# untitled.net
KiCad netlist of a schematic drawn in EAGLE
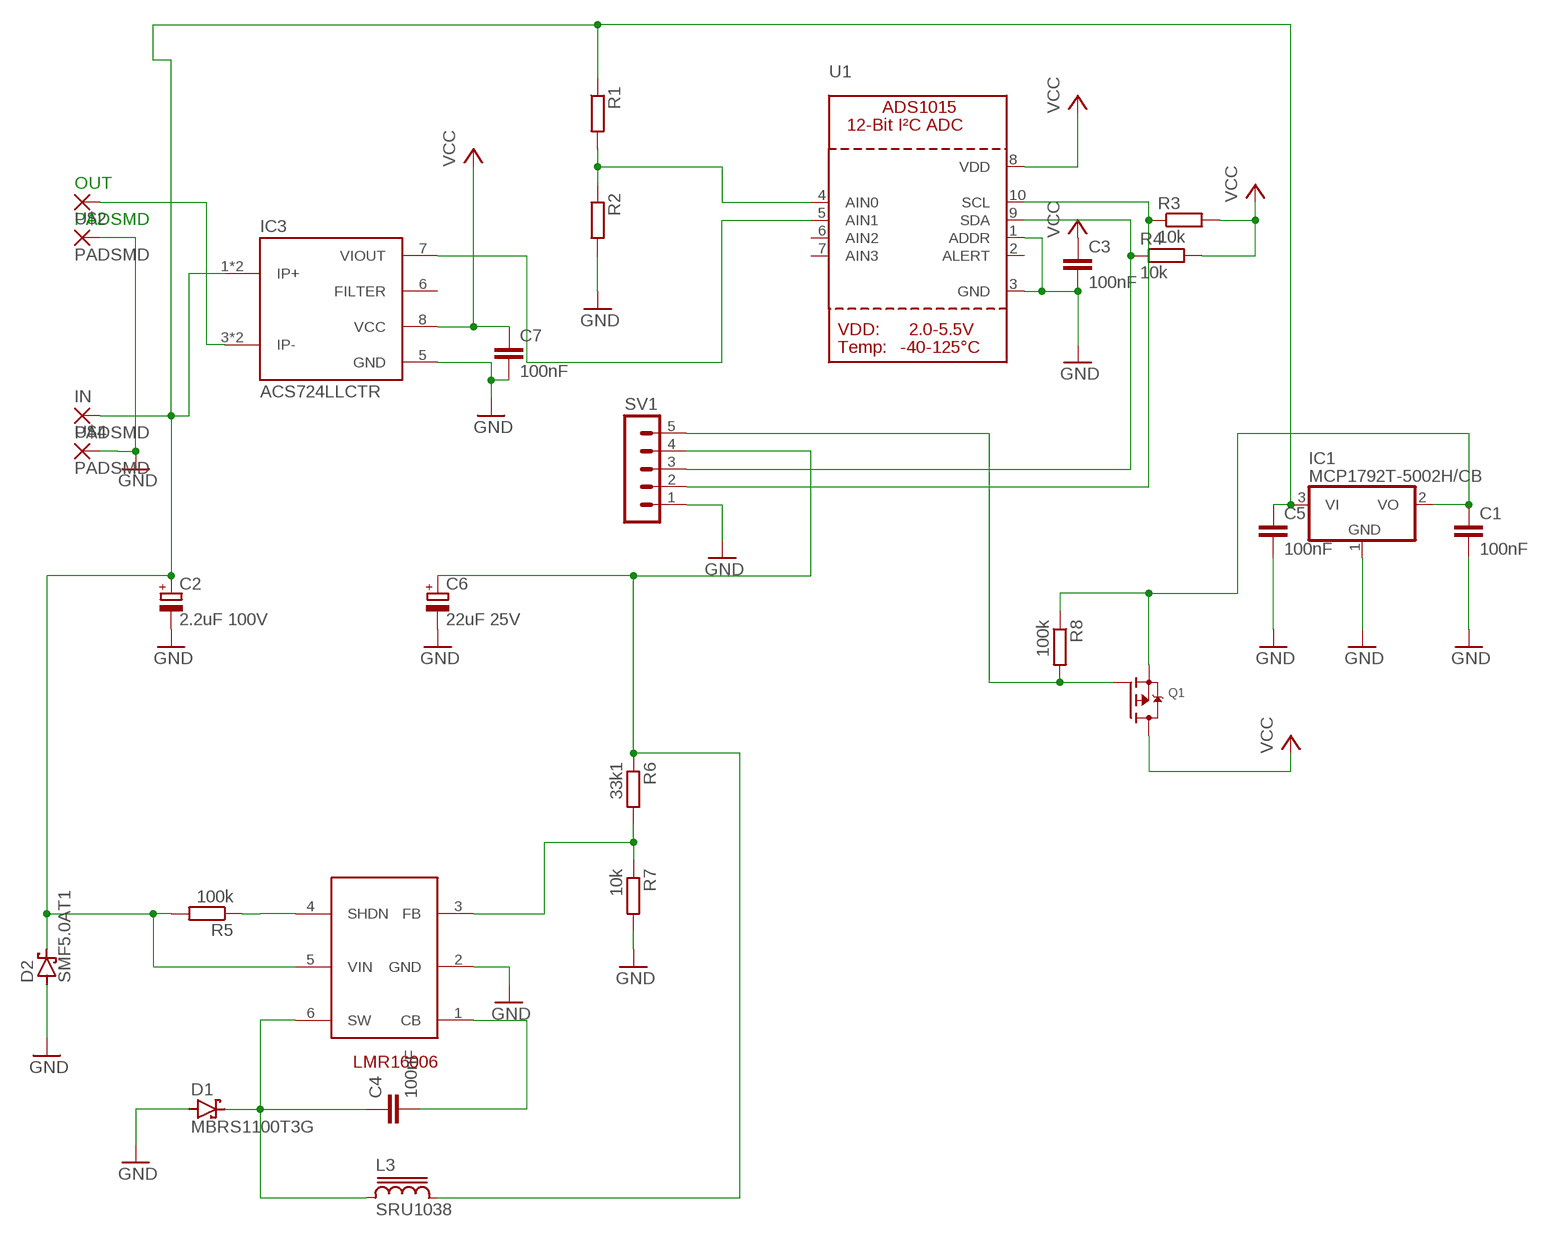
[diagram p0: schematic, sheet 1]

(export (version "E")
  (design (tool "Eeschema 10.0.6"))
  (components
    (comp (ref "C1")
      (value "100nF")
      (footprint "eagle-import:C0805")
      (libsource (lib "eagle-import") (part "C-EUC0805"))
    )
    (comp (ref "C2")
      (value "2.2uF 100V")
      (footprint "eagle-import:B_3528-21R")
      (libsource (lib "eagle-import") (part "CPOL-EUB/3528-21R"))
    )
    (comp (ref "C3")
      (value "100nF")
      (footprint "eagle-import:C0805")
      (libsource (lib "eagle-import") (part "C-EUC0805"))
    )
    (comp (ref "C4")
      (value "100nF")
      (footprint "eagle-import:C0805")
      (libsource (lib "eagle-import") (part "C-EUC0805"))
    )
    (comp (ref "C5")
      (value "100nF")
      (footprint "eagle-import:C0805")
      (libsource (lib "eagle-import") (part "C-EUC0805"))
    )
    (comp (ref "C6")
      (value "22uF 25V")
      (footprint "eagle-import:R_2012-12R")
      (libsource (lib "eagle-import") (part "CPOL-EUR/2012-12R"))
    )
    (comp (ref "C7")
      (value "100nF")
      (footprint "eagle-import:C0805")
      (libsource (lib "eagle-import") (part "C-EUC0805"))
    )
    (comp (ref "D1")
      (value "MBRS1100T3G")
      (footprint "eagle-import:SOD323_ST")
      (libsource (lib "eagle-import") (part "BAT60J"))
    )
    (comp (ref "D2")
      (value "SMF5.0AT1")
      (footprint "eagle-import:SOD123FL")
      (libsource (lib "eagle-import") (part "SMF5.0AT1"))
    )
    (comp (ref "IC1")
      (value "MCP1792T-5002H/CB")
      (footprint "eagle-import:SOT23")
      (libsource (lib "eagle-import") (part "MCP1703CB"))
    )
    (comp (ref "IC3")
      (value "ACS724LLCTR")
      (footprint "eagle-import:SO08")
      (libsource (lib "eagle-import") (part "ACS724LLCTR"))
    )
    (comp (ref "IN")
      (value "PADSMD")
      (footprint "eagle-import:PADS")
      (libsource (lib "eagle-import") (part "PADSMD"))
    )
    (comp (ref "L3")
      (value "SRU1038")
      (footprint "eagle-import:SRU1038")
      (libsource (lib "eagle-import") (part "SRU1038"))
    )
    (comp (ref "OUT")
      (value "PADSMD")
      (footprint "eagle-import:PADS")
      (libsource (lib "eagle-import") (part "PADSMD"))
    )
    (comp (ref "Q1")
      (value "MOSFET-PWIDE")
      (footprint "eagle-import:SOT23-WIDE")
      (libsource (lib "eagle-import") (part "MOSFET-PWIDE"))
    )
    (comp (ref "R1")
      (value "R-EU_R0805")
      (footprint "eagle-import:R0805")
      (libsource (lib "eagle-import") (part "R-EU_R0805"))
    )
    (comp (ref "R2")
      (value "R-EU_R0805")
      (footprint "eagle-import:R0805")
      (libsource (lib "eagle-import") (part "R-EU_R0805"))
    )
    (comp (ref "R3")
      (value "10k")
      (footprint "eagle-import:R0805")
      (libsource (lib "eagle-import") (part "R-EU_R0805"))
    )
    (comp (ref "R4")
      (value "10k")
      (footprint "eagle-import:R0805")
      (libsource (lib "eagle-import") (part "R-EU_R0805"))
    )
    (comp (ref "R5")
      (value "100k")
      (footprint "eagle-import:M0805")
      (libsource (lib "eagle-import") (part "R-EU_M0805"))
    )
    (comp (ref "R6")
      (value "33k1")
      (footprint "eagle-import:M0805")
      (libsource (lib "eagle-import") (part "R-EU_M0805"))
    )
    (comp (ref "R7")
      (value "10k")
      (footprint "eagle-import:M0805")
      (libsource (lib "eagle-import") (part "R-EU_M0805"))
    )
    (comp (ref "R8")
      (value "100k")
      (footprint "eagle-import:R0805")
      (libsource (lib "eagle-import") (part "R-EU_R0805"))
    )
    (comp (ref "SV1")
      (value "MA05-1")
      (footprint "eagle-import:MA05-1")
      (libsource (lib "eagle-import") (part "MA05-1"))
    )
    (comp (ref "U$2")
      (value "PADSMD")
      (footprint "eagle-import:PADS")
      (libsource (lib "eagle-import") (part "PADSMD"))
    )
    (comp (ref "U$4")
      (value "PADSMD")
      (footprint "eagle-import:PADS")
      (libsource (lib "eagle-import") (part "PADSMD"))
    )
    (comp (ref "U$5")
      (value "LMR16006")
      (footprint "eagle-import:TSOT23-6_DDC")
      (libsource (lib "eagle-import") (part "LMR16006"))
    )
    (comp (ref "U1")
      (value "ADC_ADS1015")
      (footprint "eagle-import:MSOP10")
      (libsource (lib "eagle-import") (part "ADC_ADS1015"))
    )
  )
  (nets
    (net (code "1") (name "GND") (class "Default")
      (node (ref "C1") (pin "2") (pinfunction "2_2") (pintype "passive"))
      (node (ref "C2") (pin "-") (pinfunction "-_-") (pintype "passive"))
      (node (ref "C3") (pin "2") (pinfunction "2_2") (pintype "passive"))
      (node (ref "C5") (pin "2") (pinfunction "2_2") (pintype "passive"))
      (node (ref "C6") (pin "-") (pinfunction "-_-") (pintype "passive"))
      (node (ref "C7") (pin "2") (pinfunction "2_2") (pintype "passive"))
      (node (ref "D1") (pin "A") (pinfunction "A_A") (pintype "passive"))
      (node (ref "D2") (pin "A") (pinfunction "A_A") (pintype "passive"))
      (node (ref "IC1") (pin "1") (pinfunction "GND_1") (pintype "passive"))
      (node (ref "IC3") (pin "5") (pinfunction "GND_5") (pintype "power_in"))
      (node (ref "R2") (pin "2") (pinfunction "2_2") (pintype "passive"))
      (node (ref "R7") (pin "2") (pinfunction "2_2") (pintype "passive"))
      (node (ref "SV1") (pin "1") (pinfunction "1_1") (pintype "passive"))
      (node (ref "U$2") (pin "P$1") (pinfunction "P_P$1") (pintype "passive"))
      (node (ref "U$4") (pin "P$1") (pinfunction "P_P$1") (pintype "passive"))
      (node (ref "U$5") (pin "2") (pinfunction "GND_2") (pintype "bidirectional"))
      (node (ref "U1") (pin "1") (pinfunction "ADDR_1") (pintype "bidirectional"))
      (node (ref "U1") (pin "3") (pinfunction "GND_3") (pintype "bidirectional"))
    )
    (net (code "2") (name "Net-(C6-Pad+)") (class "Default")
      (node (ref "C6") (pin "+") (pinfunction "+_+") (pintype "passive"))
      (node (ref "L3") (pin "2") (pinfunction "2_2") (pintype "passive"))
      (node (ref "R6") (pin "1") (pinfunction "1_1") (pintype "passive"))
      (node (ref "SV1") (pin "4") (pinfunction "4_4") (pintype "passive"))
    )
    (net (code "3") (name "Net-(IC1-VI)") (class "Default")
      (node (ref "C2") (pin "+") (pinfunction "+_+") (pintype "passive"))
      (node (ref "C5") (pin "1") (pinfunction "1_1") (pintype "passive"))
      (node (ref "D2") (pin "C") (pinfunction "C_C") (pintype "passive"))
      (node (ref "IC1") (pin "3") (pinfunction "VI_3") (pintype "input"))
      (node (ref "IC3") (pin "1") (pinfunction "IP+_1") (pintype "passive"))
      (node (ref "IC3") (pin "2") (pinfunction "IP+_2") (pintype "passive"))
      (node (ref "IN") (pin "P$1") (pinfunction "P_P$1") (pintype "passive"))
      (node (ref "R1") (pin "1") (pinfunction "1_1") (pintype "passive"))
      (node (ref "R5") (pin "2") (pinfunction "2_2") (pintype "passive"))
      (node (ref "U$5") (pin "5") (pinfunction "VIN_5") (pintype "bidirectional"))
    )
    (net (code "4") (name "Net-(IC1-VO)") (class "Default")
      (node (ref "C1") (pin "1") (pinfunction "1_1") (pintype "passive"))
      (node (ref "IC1") (pin "2") (pinfunction "VO_2") (pintype "passive"))
      (node (ref "Q1") (pin "2") (pinfunction "S_2") (pintype "passive"))
      (node (ref "R8") (pin "1") (pinfunction "1_1") (pintype "passive"))
    )
    (net (code "5") (name "Net-(IC3-VIOUT)") (class "Default")
      (node (ref "IC3") (pin "7") (pinfunction "VIOUT_7") (pintype "output"))
      (node (ref "U1") (pin "5") (pinfunction "AIN1_5") (pintype "bidirectional"))
    )
    (net (code "6") (name "Net-(OUT-P)") (class "Default")
      (node (ref "IC3") (pin "3") (pinfunction "IP-_3") (pintype "passive"))
      (node (ref "IC3") (pin "4") (pinfunction "IP-_4") (pintype "passive"))
      (node (ref "OUT") (pin "P$1") (pinfunction "P_P$1") (pintype "passive"))
    )
    (net (code "7") (name "Net-(Q1-G)") (class "Default")
      (node (ref "Q1") (pin "1") (pinfunction "G_1") (pintype "passive"))
      (node (ref "R8") (pin "2") (pinfunction "2_2") (pintype "passive"))
      (node (ref "SV1") (pin "5") (pinfunction "5_5") (pintype "passive"))
    )
    (net (code "8") (name "Net-(U$5-CB)") (class "Default")
      (node (ref "C4") (pin "2") (pinfunction "2_2") (pintype "passive"))
      (node (ref "U$5") (pin "1") (pinfunction "CB_1") (pintype "bidirectional"))
    )
    (net (code "9") (name "Net-(U$5-FB)") (class "Default")
      (node (ref "R6") (pin "2") (pinfunction "2_2") (pintype "passive"))
      (node (ref "R7") (pin "1") (pinfunction "1_1") (pintype "passive"))
      (node (ref "U$5") (pin "3") (pinfunction "FB_3") (pintype "bidirectional"))
    )
    (net (code "10") (name "Net-(U$5-SHDN)") (class "Default")
      (node (ref "R5") (pin "1") (pinfunction "1_1") (pintype "passive"))
      (node (ref "U$5") (pin "4") (pinfunction "SHDN_4") (pintype "bidirectional"))
    )
    (net (code "11") (name "Net-(U$5-SW)") (class "Default")
      (node (ref "C4") (pin "1") (pinfunction "1_1") (pintype "passive"))
      (node (ref "D1") (pin "C") (pinfunction "C_C") (pintype "passive"))
      (node (ref "L3") (pin "1") (pinfunction "1_1") (pintype "passive"))
      (node (ref "U$5") (pin "6") (pinfunction "SW_6") (pintype "bidirectional"))
    )
    (net (code "12") (name "Net-(U1-AIN0)") (class "Default")
      (node (ref "R1") (pin "2") (pinfunction "2_2") (pintype "passive"))
      (node (ref "R2") (pin "1") (pinfunction "1_1") (pintype "passive"))
      (node (ref "U1") (pin "4") (pinfunction "AIN0_4") (pintype "bidirectional"))
    )
    (net (code "13") (name "Net-(U1-SCL)") (class "Default")
      (node (ref "R3") (pin "1") (pinfunction "1_1") (pintype "passive"))
      (node (ref "SV1") (pin "2") (pinfunction "2_2") (pintype "passive"))
      (node (ref "U1") (pin "10") (pinfunction "SCL_10") (pintype "bidirectional"))
    )
    (net (code "14") (name "Net-(U1-SDA)") (class "Default")
      (node (ref "R4") (pin "1") (pinfunction "1_1") (pintype "passive"))
      (node (ref "SV1") (pin "3") (pinfunction "3_3") (pintype "passive"))
      (node (ref "U1") (pin "9") (pinfunction "SDA_9") (pintype "bidirectional"))
    )
    (net (code "15") (name "VCC") (class "Default")
      (node (ref "C3") (pin "1") (pinfunction "1_1") (pintype "passive"))
      (node (ref "C7") (pin "1") (pinfunction "1_1") (pintype "passive"))
      (node (ref "IC3") (pin "8") (pinfunction "VCC_8") (pintype "power_in"))
      (node (ref "Q1") (pin "3") (pinfunction "D_3") (pintype "passive"))
      (node (ref "R3") (pin "2") (pinfunction "2_2") (pintype "passive"))
      (node (ref "R4") (pin "2") (pinfunction "2_2") (pintype "passive"))
      (node (ref "U1") (pin "8") (pinfunction "VDD_8") (pintype "bidirectional"))
    )
    (net (code "16") (name "unconnected-(IC3-FILTER-Pad6)") (class "Default")
      (node (ref "IC3") (pin "6") (pinfunction "FILTER_6") (pintype "output"))
    )
    (net (code "17") (name "unconnected-(U1-AIN2-Pad6)") (class "Default")
      (node (ref "U1") (pin "6") (pinfunction "AIN2_6") (pintype "bidirectional"))
    )
    (net (code "18") (name "unconnected-(U1-AIN3-Pad7)") (class "Default")
      (node (ref "U1") (pin "7") (pinfunction "AIN3_7") (pintype "bidirectional"))
    )
    (net (code "19") (name "unconnected-(U1-ALERT-Pad2)") (class "Default")
      (node (ref "U1") (pin "2") (pinfunction "ALERT_2") (pintype "bidirectional"))
    )
  )
)
